# spider_2015-10-04-open-v2.net
KiCad netlist of a schematic drawn in EAGLE
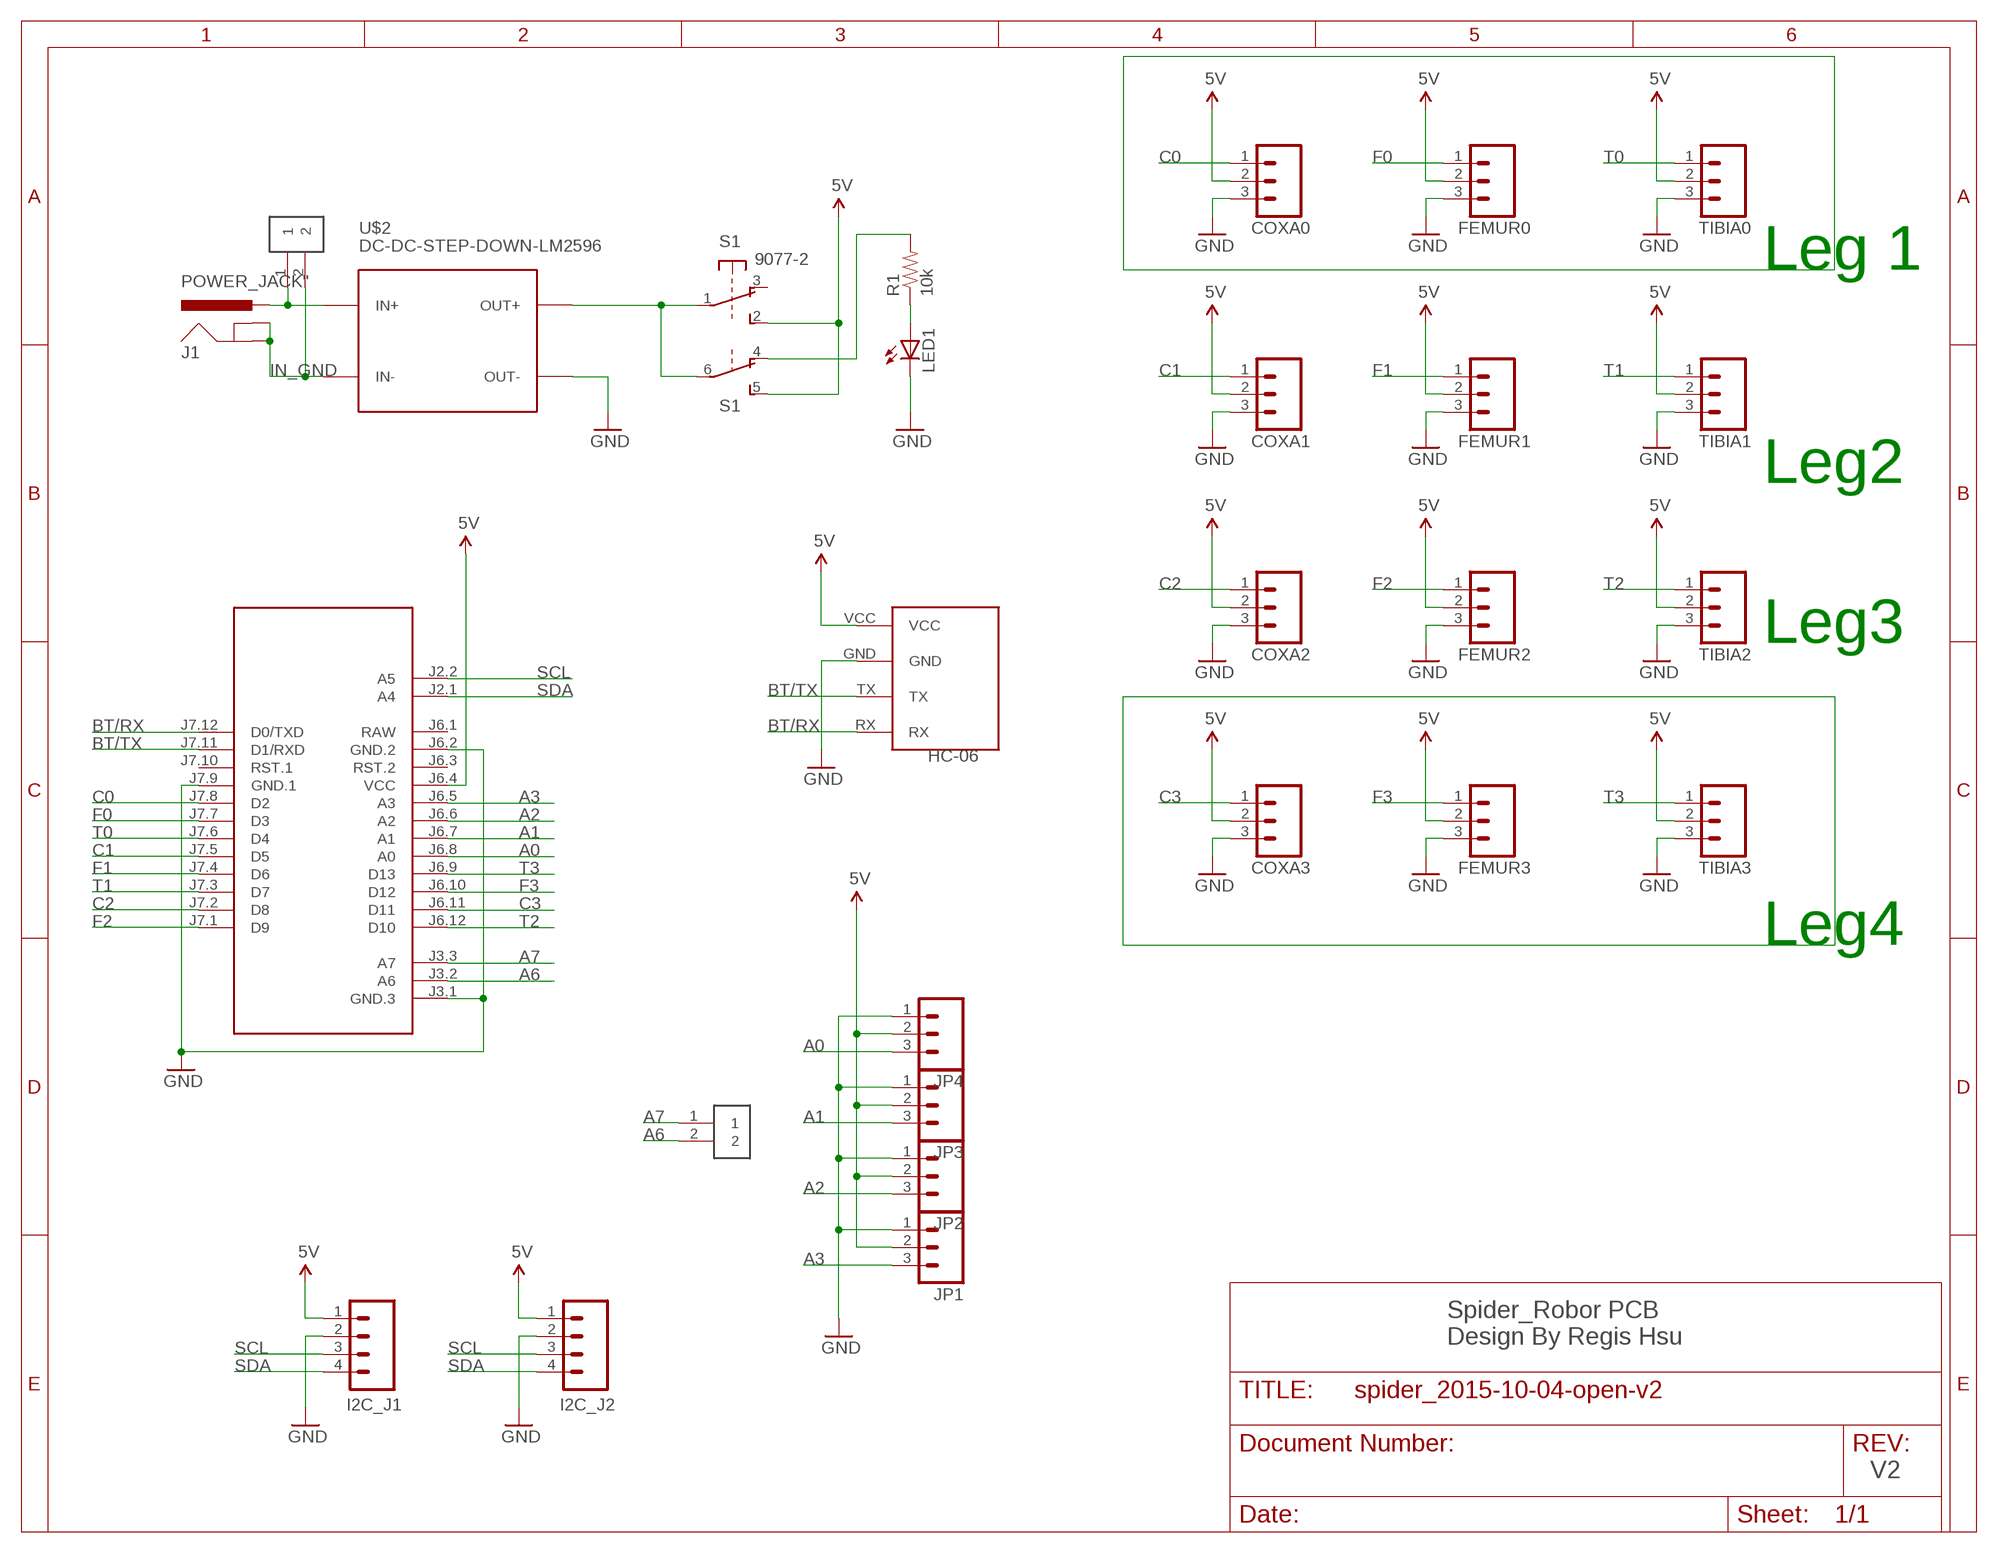
[diagram p0: schematic, sheet 1]

(export (version "E")
  (design (tool "Eeschema 10.0.6"))
  (components
    (comp (ref "COXA0")
      (value "M03PTH")
      (footprint "eagle-import:1X03")
      (libsource (lib "eagle-import") (part "M03PTH"))
    )
    (comp (ref "COXA1")
      (value "M03PTH")
      (footprint "eagle-import:1X03")
      (libsource (lib "eagle-import") (part "M03PTH"))
    )
    (comp (ref "COXA2")
      (value "M03PTH")
      (footprint "eagle-import:1X03")
      (libsource (lib "eagle-import") (part "M03PTH"))
    )
    (comp (ref "COXA3")
      (value "M03PTH")
      (footprint "eagle-import:1X03")
      (libsource (lib "eagle-import") (part "M03PTH"))
    )
    (comp (ref "FEMUR0")
      (value "M03PTH")
      (footprint "eagle-import:1X03")
      (libsource (lib "eagle-import") (part "M03PTH"))
    )
    (comp (ref "FEMUR1")
      (value "M03PTH")
      (footprint "eagle-import:1X03")
      (libsource (lib "eagle-import") (part "M03PTH"))
    )
    (comp (ref "FEMUR2")
      (value "M03PTH")
      (footprint "eagle-import:1X03")
      (libsource (lib "eagle-import") (part "M03PTH"))
    )
    (comp (ref "FEMUR3")
      (value "M03PTH")
      (footprint "eagle-import:1X03")
      (libsource (lib "eagle-import") (part "M03PTH"))
    )
    (comp (ref "HC-06")
      (value "BLUETOOTH_BOARDSTANDING")
      (footprint "eagle-import:BT_BOARD_FOOTPRINT_STANDING")
      (libsource (lib "eagle-import") (part "BLUETOOTH_BOARDSTANDING"))
    )
    (comp (ref "I2C_J1")
      (value "1X04_HEADER\"")
      (footprint "eagle-import:1X04_HEADER")
      (libsource (lib "eagle-import") (part "1X04_HEADER{dblquote}"))
    )
    (comp (ref "I2C_J2")
      (value "1X04_HEADER\"")
      (footprint "eagle-import:1X04_HEADER")
      (libsource (lib "eagle-import") (part "1X04_HEADER{dblquote}"))
    )
    (comp (ref "J1")
      (value "POWER_JACK\"")
      (footprint "eagle-import:POWER_JACK")
      (libsource (lib "eagle-import") (part "POWER_JACK{dblquote}"))
    )
    (comp (ref "JP1")
      (value "M03PTH")
      (footprint "eagle-import:1X03")
      (libsource (lib "eagle-import") (part "M03PTH"))
    )
    (comp (ref "JP2")
      (value "M03PTH")
      (footprint "eagle-import:1X03")
      (libsource (lib "eagle-import") (part "M03PTH"))
    )
    (comp (ref "JP3")
      (value "M03PTH")
      (footprint "eagle-import:1X03")
      (libsource (lib "eagle-import") (part "M03PTH"))
    )
    (comp (ref "JP4")
      (value "M03PTH")
      (footprint "eagle-import:1X03")
      (libsource (lib "eagle-import") (part "M03PTH"))
    )
    (comp (ref "LED1")
      (value "LED3MM")
      (footprint "eagle-import:LED")
      (libsource (lib "eagle-import") (part "LED3MM"))
    )
    (comp (ref "M1")
      (value "ARDUINO-PRO-MINI-5.0V")
      (footprint "eagle-import:ARDUINO-PRO-MINI")
      (libsource (lib "eagle-import") (part "ARDUINO-PRO-MINI-5.0V"))
    )
    (comp (ref "R1")
      (value "10k")
      (footprint "eagle-import:AXIAL-0.4")
      (libsource (lib "eagle-import") (part "RESISTORPTH-1/4W"))
    )
    (comp (ref "S1")
      (value "9077-2")
      (footprint "eagle-import:9077-2")
      (libsource (lib "eagle-import") (part "9077-2"))
    )
    (comp (ref "TIBIA0")
      (value "M03PTH")
      (footprint "eagle-import:1X03")
      (libsource (lib "eagle-import") (part "M03PTH"))
    )
    (comp (ref "TIBIA1")
      (value "M03PTH")
      (footprint "eagle-import:1X03")
      (libsource (lib "eagle-import") (part "M03PTH"))
    )
    (comp (ref "TIBIA2")
      (value "M03PTH")
      (footprint "eagle-import:1X03")
      (libsource (lib "eagle-import") (part "M03PTH"))
    )
    (comp (ref "TIBIA3")
      (value "M03PTH")
      (footprint "eagle-import:1X03")
      (libsource (lib "eagle-import") (part "M03PTH"))
    )
    (comp (ref "U$1")
      (value "1X02_HEADER")
      (footprint "eagle-import:1X02_HEADER")
      (libsource (lib "eagle-import") (part "1X02_HEADER"))
    )
    (comp (ref "U$2")
      (value "DC-DC-STEP-DOWN-LM2596")
      (footprint "eagle-import:DC-DC-STEP-DOWN-LM2596")
      (libsource (lib "eagle-import") (part "DC-DC-STEP-DOWN-LM2596"))
    )
    (comp (ref "U$3")
      (value "1X02_HEADER")
      (footprint "eagle-import:1X02_HEADER")
      (libsource (lib "eagle-import") (part "1X02_HEADER"))
    )
  )
  (nets
    (net (code "1") (name "/A0") (class "Default")
      (node (ref "JP4") (pin "3") (pinfunction "3_3") (pintype "passive"))
      (node (ref "M1") (pin "J6.8") (pinfunction "A0_J6.8") (pintype "bidirectional"))
    )
    (net (code "2") (name "/A1") (class "Default")
      (node (ref "JP3") (pin "3") (pinfunction "3_3") (pintype "passive"))
      (node (ref "M1") (pin "J6.7") (pinfunction "A1_J6.7") (pintype "bidirectional"))
    )
    (net (code "3") (name "/A2") (class "Default")
      (node (ref "JP2") (pin "3") (pinfunction "3_3") (pintype "passive"))
      (node (ref "M1") (pin "J6.6") (pinfunction "A2_J6.6") (pintype "bidirectional"))
    )
    (net (code "4") (name "/A3") (class "Default")
      (node (ref "JP1") (pin "3") (pinfunction "3_3") (pintype "passive"))
      (node (ref "M1") (pin "J6.5") (pinfunction "A3_J6.5") (pintype "bidirectional"))
    )
    (net (code "5") (name "/A6") (class "Default")
      (node (ref "M1") (pin "J3.2") (pinfunction "A6_J3.2") (pintype "bidirectional"))
      (node (ref "U$1") (pin "2") (pinfunction "2_2") (pintype "bidirectional"))
    )
    (net (code "6") (name "/A7") (class "Default")
      (node (ref "M1") (pin "J3.3") (pinfunction "A7_J3.3") (pintype "bidirectional"))
      (node (ref "U$1") (pin "1") (pinfunction "1_1") (pintype "bidirectional"))
    )
    (net (code "7") (name "/BT{slash}RX") (class "Default")
      (node (ref "HC-06") (pin "RX") (pinfunction "RX_RX") (pintype "bidirectional"))
      (node (ref "M1") (pin "J7.12") (pinfunction "D0/TXD_J7.12") (pintype "bidirectional"))
    )
    (net (code "8") (name "/BT{slash}TX") (class "Default")
      (node (ref "HC-06") (pin "TX") (pinfunction "TX_TX") (pintype "bidirectional"))
      (node (ref "M1") (pin "J7.11") (pinfunction "D1/RXD_J7.11") (pintype "bidirectional"))
    )
    (net (code "9") (name "/C0") (class "Default")
      (node (ref "COXA0") (pin "1") (pinfunction "1_1") (pintype "passive"))
      (node (ref "M1") (pin "J7.8") (pinfunction "D2_J7.8") (pintype "bidirectional"))
    )
    (net (code "10") (name "/C1") (class "Default")
      (node (ref "COXA1") (pin "1") (pinfunction "1_1") (pintype "passive"))
      (node (ref "M1") (pin "J7.5") (pinfunction "D5_J7.5") (pintype "bidirectional"))
    )
    (net (code "11") (name "/C2") (class "Default")
      (node (ref "COXA2") (pin "1") (pinfunction "1_1") (pintype "passive"))
      (node (ref "M1") (pin "J7.2") (pinfunction "D8_J7.2") (pintype "bidirectional"))
    )
    (net (code "12") (name "/C3") (class "Default")
      (node (ref "COXA3") (pin "1") (pinfunction "1_1") (pintype "passive"))
      (node (ref "M1") (pin "J6.11") (pinfunction "D11_J6.11") (pintype "bidirectional"))
    )
    (net (code "13") (name "/F0") (class "Default")
      (node (ref "FEMUR0") (pin "1") (pinfunction "1_1") (pintype "passive"))
      (node (ref "M1") (pin "J7.7") (pinfunction "D3_J7.7") (pintype "bidirectional"))
    )
    (net (code "14") (name "/F1") (class "Default")
      (node (ref "FEMUR1") (pin "1") (pinfunction "1_1") (pintype "passive"))
      (node (ref "M1") (pin "J7.4") (pinfunction "D6_J7.4") (pintype "bidirectional"))
    )
    (net (code "15") (name "/F2") (class "Default")
      (node (ref "FEMUR2") (pin "1") (pinfunction "1_1") (pintype "passive"))
      (node (ref "M1") (pin "J7.1") (pinfunction "D9_J7.1") (pintype "bidirectional"))
    )
    (net (code "16") (name "/F3") (class "Default")
      (node (ref "FEMUR3") (pin "1") (pinfunction "1_1") (pintype "passive"))
      (node (ref "M1") (pin "J6.10") (pinfunction "D12_J6.10") (pintype "bidirectional"))
    )
    (net (code "17") (name "/IN_GND") (class "Default")
      (node (ref "J1") (pin "GND") (pinfunction "GND_GND") (pintype "bidirectional"))
      (node (ref "J1") (pin "GNDBREAK") (pinfunction "GNDBREAK_GNDBREAK") (pintype "bidirectional"))
      (node (ref "U$2") (pin "IN-") (pinfunction "IN-_IN-") (pintype "bidirectional"))
      (node (ref "U$3") (pin "2") (pinfunction "2_2") (pintype "bidirectional"))
    )
    (net (code "18") (name "/RAW") (class "Default")
      (node (ref "M1") (pin "J6.1") (pinfunction "RAW_J6.1") (pintype "power_in"))
    )
    (net (code "19") (name "/SCL") (class "Default")
      (node (ref "I2C_J1") (pin "3") (pinfunction "3_3") (pintype "passive"))
      (node (ref "I2C_J2") (pin "3") (pinfunction "3_3") (pintype "passive"))
      (node (ref "M1") (pin "J2.2") (pinfunction "A5_J2.2") (pintype "bidirectional"))
    )
    (net (code "20") (name "/SDA") (class "Default")
      (node (ref "I2C_J1") (pin "4") (pinfunction "4_4") (pintype "passive"))
      (node (ref "I2C_J2") (pin "4") (pinfunction "4_4") (pintype "passive"))
      (node (ref "M1") (pin "J2.1") (pinfunction "A4_J2.1") (pintype "bidirectional"))
    )
    (net (code "21") (name "/T0") (class "Default")
      (node (ref "M1") (pin "J7.6") (pinfunction "D4_J7.6") (pintype "bidirectional"))
      (node (ref "TIBIA0") (pin "1") (pinfunction "1_1") (pintype "passive"))
    )
    (net (code "22") (name "/T1") (class "Default")
      (node (ref "M1") (pin "J7.3") (pinfunction "D7_J7.3") (pintype "bidirectional"))
      (node (ref "TIBIA1") (pin "1") (pinfunction "1_1") (pintype "passive"))
    )
    (net (code "23") (name "/T2") (class "Default")
      (node (ref "M1") (pin "J6.12") (pinfunction "D10_J6.12") (pintype "bidirectional"))
      (node (ref "TIBIA2") (pin "1") (pinfunction "1_1") (pintype "passive"))
    )
    (net (code "24") (name "/T3") (class "Default")
      (node (ref "M1") (pin "J6.9") (pinfunction "D13_J6.9") (pintype "bidirectional"))
      (node (ref "TIBIA3") (pin "1") (pinfunction "1_1") (pintype "passive"))
    )
    (net (code "25") (name "5V") (class "Default")
      (node (ref "COXA0") (pin "2") (pinfunction "2_2") (pintype "passive"))
      (node (ref "COXA1") (pin "2") (pinfunction "2_2") (pintype "passive"))
      (node (ref "COXA2") (pin "2") (pinfunction "2_2") (pintype "passive"))
      (node (ref "COXA3") (pin "2") (pinfunction "2_2") (pintype "passive"))
      (node (ref "FEMUR0") (pin "2") (pinfunction "2_2") (pintype "passive"))
      (node (ref "FEMUR1") (pin "2") (pinfunction "2_2") (pintype "passive"))
      (node (ref "FEMUR2") (pin "2") (pinfunction "2_2") (pintype "passive"))
      (node (ref "FEMUR3") (pin "2") (pinfunction "2_2") (pintype "passive"))
      (node (ref "HC-06") (pin "VCC") (pinfunction "VCC_VCC") (pintype "bidirectional"))
      (node (ref "I2C_J1") (pin "1") (pinfunction "1_1") (pintype "passive"))
      (node (ref "I2C_J2") (pin "1") (pinfunction "1_1") (pintype "passive"))
      (node (ref "JP1") (pin "2") (pinfunction "2_2") (pintype "passive"))
      (node (ref "JP2") (pin "2") (pinfunction "2_2") (pintype "passive"))
      (node (ref "JP3") (pin "2") (pinfunction "2_2") (pintype "passive"))
      (node (ref "JP4") (pin "2") (pinfunction "2_2") (pintype "passive"))
      (node (ref "M1") (pin "J6.4") (pinfunction "VCC_J6.4") (pintype "power_in"))
      (node (ref "S1") (pin "2") (pinfunction "S_2") (pintype "passive"))
      (node (ref "S1") (pin "5") (pinfunction "S_5") (pintype "passive"))
      (node (ref "TIBIA0") (pin "2") (pinfunction "2_2") (pintype "passive"))
      (node (ref "TIBIA1") (pin "2") (pinfunction "2_2") (pintype "passive"))
      (node (ref "TIBIA2") (pin "2") (pinfunction "2_2") (pintype "passive"))
      (node (ref "TIBIA3") (pin "2") (pinfunction "2_2") (pintype "passive"))
    )
    (net (code "26") (name "GND") (class "Default")
      (node (ref "COXA0") (pin "3") (pinfunction "3_3") (pintype "passive"))
      (node (ref "COXA1") (pin "3") (pinfunction "3_3") (pintype "passive"))
      (node (ref "COXA2") (pin "3") (pinfunction "3_3") (pintype "passive"))
      (node (ref "COXA3") (pin "3") (pinfunction "3_3") (pintype "passive"))
      (node (ref "FEMUR0") (pin "3") (pinfunction "3_3") (pintype "passive"))
      (node (ref "FEMUR1") (pin "3") (pinfunction "3_3") (pintype "passive"))
      (node (ref "FEMUR2") (pin "3") (pinfunction "3_3") (pintype "passive"))
      (node (ref "FEMUR3") (pin "3") (pinfunction "3_3") (pintype "passive"))
      (node (ref "HC-06") (pin "GND") (pinfunction "GND_GND") (pintype "bidirectional"))
      (node (ref "I2C_J1") (pin "2") (pinfunction "2_2") (pintype "passive"))
      (node (ref "I2C_J2") (pin "2") (pinfunction "2_2") (pintype "passive"))
      (node (ref "JP1") (pin "1") (pinfunction "1_1") (pintype "passive"))
      (node (ref "JP2") (pin "1") (pinfunction "1_1") (pintype "passive"))
      (node (ref "JP3") (pin "1") (pinfunction "1_1") (pintype "passive"))
      (node (ref "JP4") (pin "1") (pinfunction "1_1") (pintype "passive"))
      (node (ref "LED1") (pin "K") (pinfunction "C_K") (pintype "passive"))
      (node (ref "M1") (pin "J3.1") (pinfunction "GND.3_J3.1") (pintype "bidirectional"))
      (node (ref "M1") (pin "J6.2") (pinfunction "GND.2_J6.2") (pintype "power_in"))
      (node (ref "M1") (pin "J7.9") (pinfunction "GND.1_J7.9") (pintype "power_in"))
      (node (ref "TIBIA0") (pin "3") (pinfunction "3_3") (pintype "passive"))
      (node (ref "TIBIA1") (pin "3") (pinfunction "3_3") (pintype "passive"))
      (node (ref "TIBIA2") (pin "3") (pinfunction "3_3") (pintype "passive"))
      (node (ref "TIBIA3") (pin "3") (pinfunction "3_3") (pintype "passive"))
      (node (ref "U$2") (pin "OUT-") (pinfunction "OUT-_OUT-") (pintype "bidirectional"))
    )
    (net (code "27") (name "Net-(J1-PadPWR)") (class "Default")
      (node (ref "J1") (pin "PWR") (pinfunction "PWR_PWR") (pintype "bidirectional"))
      (node (ref "U$2") (pin "IN+") (pinfunction "IN+_IN+") (pintype "bidirectional"))
      (node (ref "U$3") (pin "1") (pinfunction "1_1") (pintype "bidirectional"))
    )
    (net (code "28") (name "Net-(R1-1)") (class "Default")
      (node (ref "LED1") (pin "A") (pinfunction "A_A") (pintype "passive"))
      (node (ref "R1") (pin "P$1") (pinfunction "1_P$1") (pintype "passive"))
    )
    (net (code "29") (name "Net-(R1-2)") (class "Default")
      (node (ref "R1") (pin "P$2") (pinfunction "2_P$2") (pintype "passive"))
      (node (ref "S1") (pin "4") (pinfunction "O_4") (pintype "passive"))
    )
    (net (code "30") (name "Net-(S1A-P)") (class "Default")
      (node (ref "S1") (pin "1") (pinfunction "P_1") (pintype "passive"))
      (node (ref "S1") (pin "6") (pinfunction "P_6") (pintype "passive"))
      (node (ref "U$2") (pin "OUT+") (pinfunction "OUT+_OUT+") (pintype "bidirectional"))
    )
    (net (code "31") (name "unconnected-(M1-RST.1-PadJ7.10)") (class "Default")
      (node (ref "M1") (pin "J7.10") (pinfunction "RST.1_J7.10") (pintype "bidirectional"))
    )
    (net (code "32") (name "unconnected-(M1-RST.2-PadJ6.3)") (class "Default")
      (node (ref "M1") (pin "J6.3") (pinfunction "RST.2_J6.3") (pintype "bidirectional"))
    )
    (net (code "33") (name "unconnected-(S1A-O-Pad3)") (class "Default")
      (node (ref "S1") (pin "3") (pinfunction "O_3") (pintype "passive"))
    )
  )
)
